# PMIC.net
KiCad netlist of a schematic drawn in Altium Designer
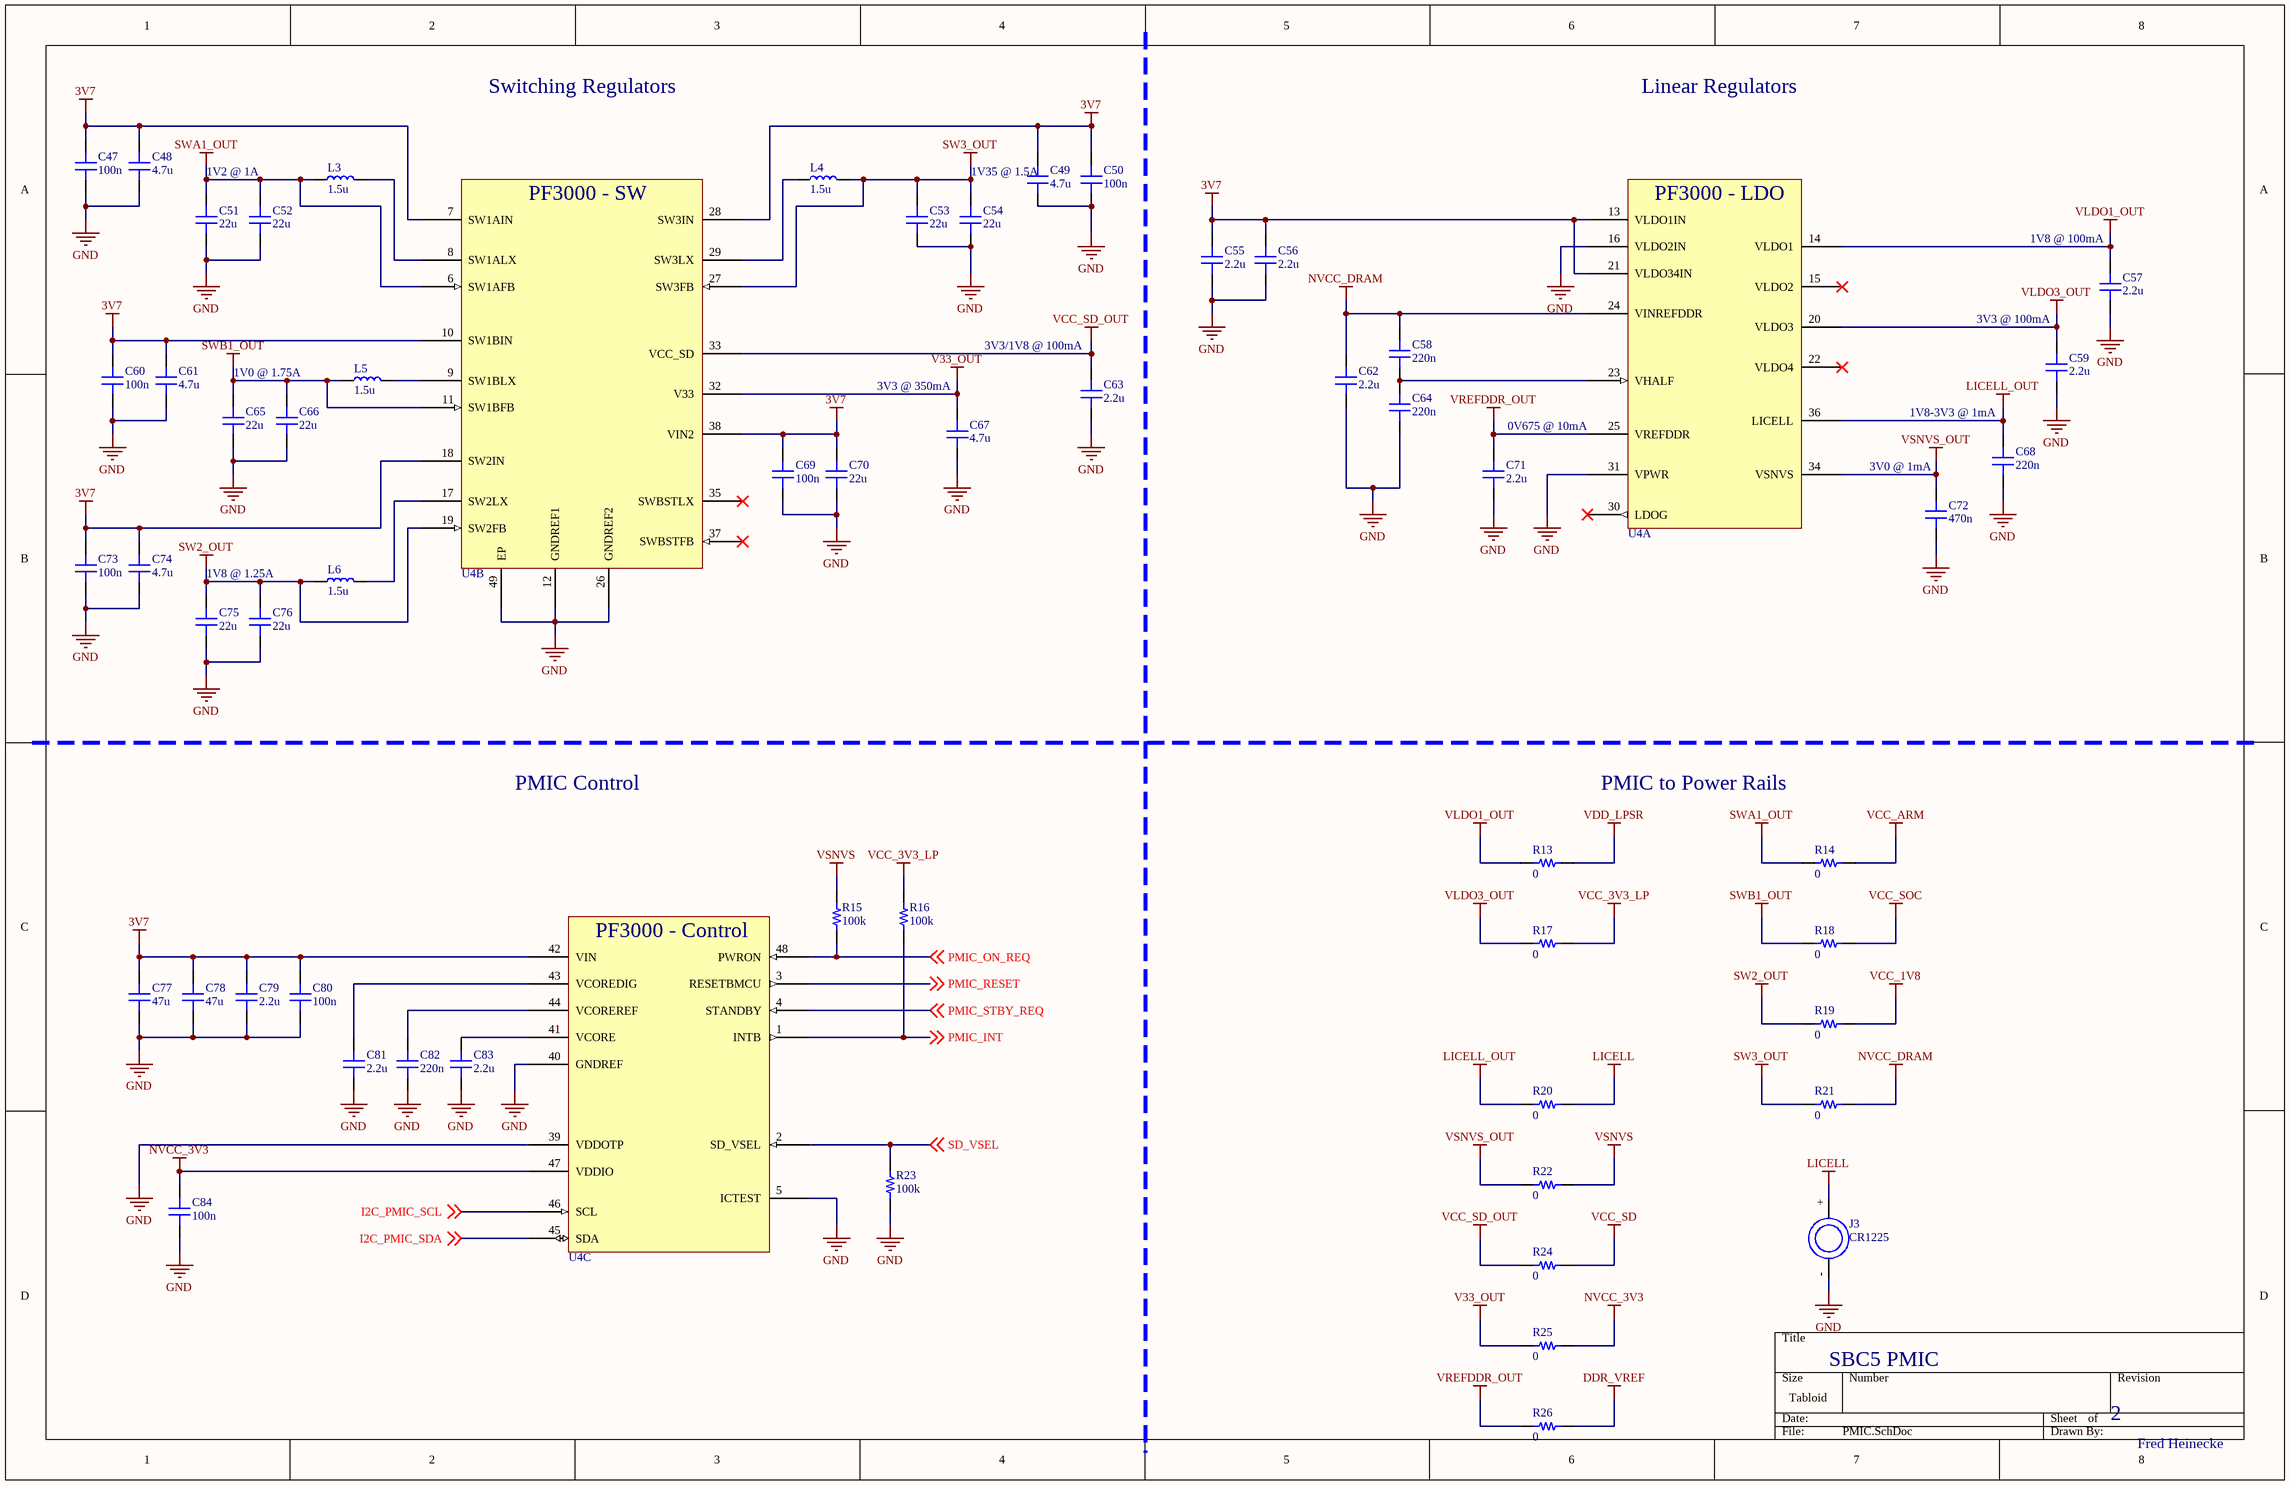
[diagram p0: PMIC.SchDoc]

(export (version "E")
  (design (tool "Eeschema 10.0.6"))
  (components
    (comp (ref "C47")
      (value "100n")
      (footprint "C0201")
      (description "Multilayer Ceramic Capacitors MLCC - SMD/SMT 0201 0.10uF 16volts *Derate Voltage/Temp")
      (fields
        (field (name "MANUFACTURER") "Murata")
        (field (name "MANUFACTURER PART NUMBER") "GRM033R61C104KE84D")
      )
      (libsource (lib "SBC5") (part "GRM033R61C104KE84D"))
    )
    (comp (ref "C48")
      (value "4.7u")
      (footprint "C0603")
      (description "Cap Ceramic 4.7uF 10V X5R 10% Pad SMD 0603 85C T/R")
      (fields
        (field (name "MANUFACTURER") "Samsung")
        (field (name "MANUFACTURER PART NUMBER") "CL10A475KP8NNNC")
      )
      (libsource (lib "SBC5") (part "CL10A475KP8NNNC"))
    )
    (comp (ref "C49")
      (value "4.7u")
      (footprint "C0603")
      (description "Cap Ceramic 4.7uF 10V X5R 10% Pad SMD 0603 85C T/R")
      (fields
        (field (name "MANUFACTURER") "Samsung")
        (field (name "MANUFACTURER PART NUMBER") "CL10A475KP8NNNC")
      )
      (libsource (lib "SBC5") (part "CL10A475KP8NNNC"))
    )
    (comp (ref "C50")
      (value "100n")
      (footprint "C0201")
      (description "Multilayer Ceramic Capacitors MLCC - SMD/SMT 0201 0.10uF 16volts *Derate Voltage/Temp")
      (fields
        (field (name "MANUFACTURER") "Murata")
        (field (name "MANUFACTURER PART NUMBER") "GRM033R61C104KE84D")
      )
      (libsource (lib "SBC5") (part "GRM033R61C104KE84D"))
    )
    (comp (ref "C51")
      (value "22u")
      (footprint "C0603")
      (description "0603 22 uF 10 V ±20% Tolerance X5R Multilayer Ceramic Chip Capacitor")
      (fields
        (field (name "MANUFACTURER") "Murata")
        (field (name "MANUFACTURER PART NUMBER") "GRM188R61A226ME15D")
      )
      (libsource (lib "SBC5") (part "GRM188R61A226ME15D"))
    )
    (comp (ref "C52")
      (value "22u")
      (footprint "C0603")
      (description "0603 22 uF 10 V ±20% Tolerance X5R Multilayer Ceramic Chip Capacitor")
      (fields
        (field (name "MANUFACTURER") "Murata")
        (field (name "MANUFACTURER PART NUMBER") "GRM188R61A226ME15D")
      )
      (libsource (lib "SBC5") (part "GRM188R61A226ME15D"))
    )
    (comp (ref "C53")
      (value "22u")
      (footprint "C0603")
      (description "0603 22 uF 10 V ±20% Tolerance X5R Multilayer Ceramic Chip Capacitor")
      (fields
        (field (name "MANUFACTURER") "Murata")
        (field (name "MANUFACTURER PART NUMBER") "GRM188R61A226ME15D")
      )
      (libsource (lib "SBC5") (part "GRM188R61A226ME15D"))
    )
    (comp (ref "C54")
      (value "22u")
      (footprint "C0603")
      (description "0603 22 uF 10 V ±20% Tolerance X5R Multilayer Ceramic Chip Capacitor")
      (fields
        (field (name "MANUFACTURER") "Murata")
        (field (name "MANUFACTURER PART NUMBER") "GRM188R61A226ME15D")
      )
      (libsource (lib "SBC5") (part "GRM188R61A226ME15D"))
    )
    (comp (ref "C55")
      (value "2.2u")
      (footprint "C0402")
      (description "TAIYO YUDEN         LMK105BJ225MV-F            CERAMIC CAPACITOR, 2.2UF, 10V, X5R, 20%, 0402")
      (fields
        (field (name "MANUFACTURER") "Taiyo Yuden")
        (field (name "MANUFACTURER PART NUMBER") "LMK105BJ225MV-F")
      )
      (libsource (lib "SBC5") (part "LMK105BJ225MV-F"))
    )
    (comp (ref "C56")
      (value "2.2u")
      (footprint "C0402")
      (description "TAIYO YUDEN         LMK105BJ225MV-F            CERAMIC CAPACITOR, 2.2UF, 10V, X5R, 20%, 0402")
      (fields
        (field (name "MANUFACTURER") "Taiyo Yuden")
        (field (name "MANUFACTURER PART NUMBER") "LMK105BJ225MV-F")
      )
      (libsource (lib "SBC5") (part "LMK105BJ225MV-F"))
    )
    (comp (ref "C57")
      (value "2.2u")
      (footprint "C0402")
      (description "TAIYO YUDEN         LMK105BJ225MV-F            CERAMIC CAPACITOR, 2.2UF, 10V, X5R, 20%, 0402")
      (fields
        (field (name "MANUFACTURER") "Taiyo Yuden")
        (field (name "MANUFACTURER PART NUMBER") "LMK105BJ225MV-F")
      )
      (libsource (lib "SBC5") (part "LMK105BJ225MV-F"))
    )
    (comp (ref "C58")
      (value "220n")
      (footprint "C0201")
      (description "Cap Ceramic Monolithic 0.22uF 16VDC 10% SMD Paper T/R")
      (fields
        (field (name "MANUFACTURER") "Murata")
        (field (name "MANUFACTURER PART NUMBER") "GRM033R61C224KE14D")
      )
      (libsource (lib "SBC5") (part "GRM033R61C224KE14D"))
    )
    (comp (ref "C59")
      (value "2.2u")
      (footprint "C0402")
      (description "TAIYO YUDEN         LMK105BJ225MV-F            CERAMIC CAPACITOR, 2.2UF, 10V, X5R, 20%, 0402")
      (fields
        (field (name "MANUFACTURER") "Taiyo Yuden")
        (field (name "MANUFACTURER PART NUMBER") "LMK105BJ225MV-F")
      )
      (libsource (lib "SBC5") (part "LMK105BJ225MV-F"))
    )
    (comp (ref "C60")
      (value "100n")
      (footprint "C0201")
      (description "Multilayer Ceramic Capacitors MLCC - SMD/SMT 0201 0.10uF 16volts *Derate Voltage/Temp")
      (fields
        (field (name "MANUFACTURER") "Murata")
        (field (name "MANUFACTURER PART NUMBER") "GRM033R61C104KE84D")
      )
      (libsource (lib "SBC5") (part "GRM033R61C104KE84D"))
    )
    (comp (ref "C61")
      (value "4.7u")
      (footprint "C0603")
      (description "Cap Ceramic 4.7uF 10V X5R 10% Pad SMD 0603 85C T/R")
      (fields
        (field (name "MANUFACTURER") "Samsung")
        (field (name "MANUFACTURER PART NUMBER") "CL10A475KP8NNNC")
      )
      (libsource (lib "SBC5") (part "CL10A475KP8NNNC"))
    )
    (comp (ref "C62")
      (value "2.2u")
      (footprint "C0402")
      (description "TAIYO YUDEN         LMK105BJ225MV-F            CERAMIC CAPACITOR, 2.2UF, 10V, X5R, 20%, 0402")
      (fields
        (field (name "MANUFACTURER") "Taiyo Yuden")
        (field (name "MANUFACTURER PART NUMBER") "LMK105BJ225MV-F")
      )
      (libsource (lib "SBC5") (part "LMK105BJ225MV-F"))
    )
    (comp (ref "C63")
      (value "2.2u")
      (footprint "C0402")
      (description "TAIYO YUDEN         LMK105BJ225MV-F            CERAMIC CAPACITOR, 2.2UF, 10V, X5R, 20%, 0402")
      (fields
        (field (name "MANUFACTURER") "Taiyo Yuden")
        (field (name "MANUFACTURER PART NUMBER") "LMK105BJ225MV-F")
      )
      (libsource (lib "SBC5") (part "LMK105BJ225MV-F"))
    )
    (comp (ref "C64")
      (value "220n")
      (footprint "C0201")
      (description "Cap Ceramic Monolithic 0.22uF 16VDC 10% SMD Paper T/R")
      (fields
        (field (name "MANUFACTURER") "Murata")
        (field (name "MANUFACTURER PART NUMBER") "GRM033R61C224KE14D")
      )
      (libsource (lib "SBC5") (part "GRM033R61C224KE14D"))
    )
    (comp (ref "C65")
      (value "22u")
      (footprint "C0603")
      (description "0603 22 uF 10 V ±20% Tolerance X5R Multilayer Ceramic Chip Capacitor")
      (fields
        (field (name "MANUFACTURER") "Murata")
        (field (name "MANUFACTURER PART NUMBER") "GRM188R61A226ME15D")
      )
      (libsource (lib "SBC5") (part "GRM188R61A226ME15D"))
    )
    (comp (ref "C66")
      (value "22u")
      (footprint "C0603")
      (description "0603 22 uF 10 V ±20% Tolerance X5R Multilayer Ceramic Chip Capacitor")
      (fields
        (field (name "MANUFACTURER") "Murata")
        (field (name "MANUFACTURER PART NUMBER") "GRM188R61A226ME15D")
      )
      (libsource (lib "SBC5") (part "GRM188R61A226ME15D"))
    )
    (comp (ref "C67")
      (value "4.7u")
      (footprint "C0603")
      (description "Cap Ceramic 4.7uF 10V X5R 10% Pad SMD 0603 85C T/R")
      (fields
        (field (name "MANUFACTURER") "Samsung")
        (field (name "MANUFACTURER PART NUMBER") "CL10A475KP8NNNC")
      )
      (libsource (lib "SBC5") (part "CL10A475KP8NNNC"))
    )
    (comp (ref "C68")
      (value "220n")
      (footprint "C0201")
      (description "Cap Ceramic Monolithic 0.22uF 16VDC 10% SMD Paper T/R")
      (fields
        (field (name "MANUFACTURER") "Murata")
        (field (name "MANUFACTURER PART NUMBER") "GRM033R61C224KE14D")
      )
      (libsource (lib "SBC5") (part "GRM033R61C224KE14D"))
    )
    (comp (ref "C69")
      (value "100n")
      (footprint "C0201")
      (description "Multilayer Ceramic Capacitors MLCC - SMD/SMT 0201 0.10uF 16volts *Derate Voltage/Temp")
      (fields
        (field (name "MANUFACTURER") "Murata")
        (field (name "MANUFACTURER PART NUMBER") "GRM033R61C104KE84D")
      )
      (libsource (lib "SBC5") (part "GRM033R61C104KE84D"))
    )
    (comp (ref "C70")
      (value "22u")
      (footprint "C0603")
      (description "0603 22 uF 10 V ±20% Tolerance X5R Multilayer Ceramic Chip Capacitor")
      (fields
        (field (name "MANUFACTURER") "Murata")
        (field (name "MANUFACTURER PART NUMBER") "GRM188R61A226ME15D")
      )
      (libsource (lib "SBC5") (part "GRM188R61A226ME15D"))
    )
    (comp (ref "C71")
      (value "2.2u")
      (footprint "C0402")
      (description "TAIYO YUDEN         LMK105BJ225MV-F            CERAMIC CAPACITOR, 2.2UF, 10V, X5R, 20%, 0402")
      (fields
        (field (name "MANUFACTURER") "Taiyo Yuden")
        (field (name "MANUFACTURER PART NUMBER") "LMK105BJ225MV-F")
      )
      (libsource (lib "SBC5") (part "LMK105BJ225MV-F"))
    )
    (comp (ref "C72")
      (value "470n")
      (footprint "C0402")
      (description "Cap Ceramic 0.47uF 10V X5R 10% SMD 0402 85C T/R")
      (fields
        (field (name "MANUFACTURER") "Samsung")
        (field (name "MANUFACTURER PART NUMBER") "CL05A474KP5NNNC")
      )
      (libsource (lib "SBC5") (part "CL05A474KP5NNNC"))
    )
    (comp (ref "C73")
      (value "100n")
      (footprint "C0201")
      (description "Multilayer Ceramic Capacitors MLCC - SMD/SMT 0201 0.10uF 16volts *Derate Voltage/Temp")
      (fields
        (field (name "MANUFACTURER") "Murata")
        (field (name "MANUFACTURER PART NUMBER") "GRM033R61C104KE84D")
      )
      (libsource (lib "SBC5") (part "GRM033R61C104KE84D"))
    )
    (comp (ref "C74")
      (value "4.7u")
      (footprint "C0603")
      (description "Cap Ceramic 4.7uF 10V X5R 10% Pad SMD 0603 85C T/R")
      (fields
        (field (name "MANUFACTURER") "Samsung")
        (field (name "MANUFACTURER PART NUMBER") "CL10A475KP8NNNC")
      )
      (libsource (lib "SBC5") (part "CL10A475KP8NNNC"))
    )
    (comp (ref "C75")
      (value "22u")
      (footprint "C0603")
      (description "0603 22 uF 10 V ±20% Tolerance X5R Multilayer Ceramic Chip Capacitor")
      (fields
        (field (name "MANUFACTURER") "Murata")
        (field (name "MANUFACTURER PART NUMBER") "GRM188R61A226ME15D")
      )
      (libsource (lib "SBC5") (part "GRM188R61A226ME15D"))
    )
    (comp (ref "C76")
      (value "22u")
      (footprint "C0603")
      (description "0603 22 uF 10 V ±20% Tolerance X5R Multilayer Ceramic Chip Capacitor")
      (fields
        (field (name "MANUFACTURER") "Murata")
        (field (name "MANUFACTURER PART NUMBER") "GRM188R61A226ME15D")
      )
      (libsource (lib "SBC5") (part "GRM188R61A226ME15D"))
    )
    (comp (ref "C77")
      (value "47u")
      (footprint "C0805")
      (fields
        (field (name "MANUFACTURER") "TDK")
        (field (name "MANUFACTURER PART NUMBER") "C2012X5R1A476M125AC")
        (field (name "TOLERANCE") "20%")
      )
      (libsource (lib "SBC5") (part "C2012X5R1A476M125AC"))
    )
    (comp (ref "C78")
      (value "47u")
      (footprint "C0805")
      (fields
        (field (name "MANUFACTURER") "TDK")
        (field (name "MANUFACTURER PART NUMBER") "C2012X5R1A476M125AC")
        (field (name "TOLERANCE") "20%")
      )
      (libsource (lib "SBC5") (part "C2012X5R1A476M125AC"))
    )
    (comp (ref "C79")
      (value "2.2u")
      (footprint "C0402")
      (description "TAIYO YUDEN         LMK105BJ225MV-F            CERAMIC CAPACITOR, 2.2UF, 10V, X5R, 20%, 0402")
      (fields
        (field (name "MANUFACTURER") "Taiyo Yuden")
        (field (name "MANUFACTURER PART NUMBER") "LMK105BJ225MV-F")
      )
      (libsource (lib "SBC5") (part "LMK105BJ225MV-F"))
    )
    (comp (ref "C80")
      (value "100n")
      (footprint "C0201")
      (description "Multilayer Ceramic Capacitors MLCC - SMD/SMT 0201 0.10uF 16volts *Derate Voltage/Temp")
      (fields
        (field (name "MANUFACTURER") "Murata")
        (field (name "MANUFACTURER PART NUMBER") "GRM033R61C104KE84D")
      )
      (libsource (lib "SBC5") (part "GRM033R61C104KE84D"))
    )
    (comp (ref "C81")
      (value "2.2u")
      (footprint "C0402")
      (description "TAIYO YUDEN         LMK105BJ225MV-F            CERAMIC CAPACITOR, 2.2UF, 10V, X5R, 20%, 0402")
      (fields
        (field (name "MANUFACTURER") "Taiyo Yuden")
        (field (name "MANUFACTURER PART NUMBER") "LMK105BJ225MV-F")
      )
      (libsource (lib "SBC5") (part "LMK105BJ225MV-F"))
    )
    (comp (ref "C82")
      (value "220n")
      (footprint "C0201")
      (description "Cap Ceramic Monolithic 0.22uF 16VDC 10% SMD Paper T/R")
      (fields
        (field (name "MANUFACTURER") "Murata")
        (field (name "MANUFACTURER PART NUMBER") "GRM033R61C224KE14D")
      )
      (libsource (lib "SBC5") (part "GRM033R61C224KE14D"))
    )
    (comp (ref "C83")
      (value "2.2u")
      (footprint "C0402")
      (description "TAIYO YUDEN         LMK105BJ225MV-F            CERAMIC CAPACITOR, 2.2UF, 10V, X5R, 20%, 0402")
      (fields
        (field (name "MANUFACTURER") "Taiyo Yuden")
        (field (name "MANUFACTURER PART NUMBER") "LMK105BJ225MV-F")
      )
      (libsource (lib "SBC5") (part "LMK105BJ225MV-F"))
    )
    (comp (ref "C84")
      (value "100n")
      (footprint "C0201")
      (description "Multilayer Ceramic Capacitors MLCC - SMD/SMT 0201 0.10uF 16volts *Derate Voltage/Temp")
      (fields
        (field (name "MANUFACTURER") "Murata")
        (field (name "MANUFACTURER PART NUMBER") "GRM033R61C104KE84D")
      )
      (libsource (lib "SBC5") (part "GRM033R61C104KE84D"))
    )
    (comp (ref "J3")
      (value "CR1225")
      (footprint "BAT-HLD-012-THM")
      (description "BATTERY RETAINER COIN PC PIN")
      (fields
        (field (name "MANUFACTURER") "Linx")
        (field (name "MANUFACTURER PART NUMBER") "BAT-HLD-012-THM")
      )
      (libsource (lib "SBC5") (part "BAT-HLD-012-THM"))
    )
    (comp (ref "L3")
      (value "1.5u")
      (footprint "L0806")
      (description "Inductor Power Shielded Wirewound 1.5uH 20% 1MHz Metal 2.1A 0.091Ohm DCR 0806 T/R")
      (fields
        (field (name "MANUFACTURER") "Murata")
        (field (name "MANUFACTURER PART NUMBER") "DFE201610E-1R5M=P2")
      )
      (libsource (lib "SBC5") (part "DFE201610E-1R5M=P2"))
    )
    (comp (ref "L4")
      (value "1.5u")
      (footprint "L0806")
      (description "Inductor Power Shielded Wirewound 1.5uH 20% 1MHz Metal 2.1A 0.091Ohm DCR 0806 T/R")
      (fields
        (field (name "MANUFACTURER") "Murata")
        (field (name "MANUFACTURER PART NUMBER") "DFE201610E-1R5M=P2")
      )
      (libsource (lib "") (part "DFE201610E-1R5M=P2_1"))
    )
    (comp (ref "L5")
      (value "1.5u")
      (footprint "L0806")
      (description "Inductor Power Shielded Wirewound 1.5uH 20% 1MHz Metal 2.1A 0.091Ohm DCR 0806 T/R")
      (fields
        (field (name "MANUFACTURER") "Murata")
        (field (name "MANUFACTURER PART NUMBER") "DFE201610E-1R5M=P2")
      )
      (libsource (lib "SBC5") (part "DFE201610E-1R5M=P2"))
    )
    (comp (ref "L6")
      (value "1.5u")
      (footprint "L0806")
      (description "Inductor Power Shielded Wirewound 1.5uH 20% 1MHz Metal 2.1A 0.091Ohm DCR 0806 T/R")
      (fields
        (field (name "MANUFACTURER") "Murata")
        (field (name "MANUFACTURER PART NUMBER") "DFE201610E-1R5M=P2")
      )
      (libsource (lib "SBC5") (part "DFE201610E-1R5M=P2"))
    )
    (comp (ref "R13")
      (value "0")
      (footprint "R0402")
      (description "RES 0 OHM JUMPER 1/16W 0402")
      (fields
        (field (name "MANUFACTURER") "Stackpole Electronics")
        (field (name "MANUFACTURER PART NUMBER") "RMCF0402ZT0R00")
      )
      (libsource (lib "SBC5") (part "RMCF0402ZT0R00"))
    )
    (comp (ref "R14")
      (value "0")
      (footprint "R0402")
      (description "RES 0 OHM JUMPER 1/16W 0402")
      (fields
        (field (name "MANUFACTURER") "Stackpole Electronics")
        (field (name "MANUFACTURER PART NUMBER") "RMCF0402ZT0R00")
      )
      (libsource (lib "SBC5") (part "RMCF0402ZT0R00"))
    )
    (comp (ref "R15")
      (value "100k")
      (footprint "R0201")
      (description "PANASONIC - ERJ1GNF1003C - RES, 100K, 1%, 0.05W, 0201, THICK FILM")
      (fields
        (field (name "MANUFACTURER") "Panasonic")
        (field (name "MANUFACTURER PART NUMBER") "ERJ-1GNF1003C")
      )
      (libsource (lib "SBC5") (part "ERJ-1GNF1003C"))
    )
    (comp (ref "R16")
      (value "100k")
      (footprint "R0201")
      (description "PANASONIC - ERJ1GNF1003C - RES, 100K, 1%, 0.05W, 0201, THICK FILM")
      (fields
        (field (name "MANUFACTURER") "Panasonic")
        (field (name "MANUFACTURER PART NUMBER") "ERJ-1GNF1003C")
      )
      (libsource (lib "SBC5") (part "ERJ-1GNF1003C"))
    )
    (comp (ref "R17")
      (value "0")
      (footprint "R0402")
      (description "RES 0 OHM JUMPER 1/16W 0402")
      (fields
        (field (name "MANUFACTURER") "Stackpole Electronics")
        (field (name "MANUFACTURER PART NUMBER") "RMCF0402ZT0R00")
      )
      (libsource (lib "SBC5") (part "RMCF0402ZT0R00"))
    )
    (comp (ref "R18")
      (value "0")
      (footprint "R0402")
      (description "RES 0 OHM JUMPER 1/16W 0402")
      (fields
        (field (name "MANUFACTURER") "Stackpole Electronics")
        (field (name "MANUFACTURER PART NUMBER") "RMCF0402ZT0R00")
      )
      (libsource (lib "SBC5") (part "RMCF0402ZT0R00"))
    )
    (comp (ref "R19")
      (value "0")
      (footprint "R0402")
      (description "RES 0 OHM JUMPER 1/16W 0402")
      (fields
        (field (name "MANUFACTURER") "Stackpole Electronics")
        (field (name "MANUFACTURER PART NUMBER") "RMCF0402ZT0R00")
      )
      (libsource (lib "SBC5") (part "RMCF0402ZT0R00"))
    )
    (comp (ref "R20")
      (value "0")
      (footprint "R0402")
      (description "RES 0 OHM JUMPER 1/16W 0402")
      (fields
        (field (name "MANUFACTURER") "Stackpole Electronics")
        (field (name "MANUFACTURER PART NUMBER") "RMCF0402ZT0R00")
      )
      (libsource (lib "SBC5") (part "RMCF0402ZT0R00"))
    )
    (comp (ref "R21")
      (value "0")
      (footprint "R0402")
      (description "RES 0 OHM JUMPER 1/16W 0402")
      (fields
        (field (name "MANUFACTURER") "Stackpole Electronics")
        (field (name "MANUFACTURER PART NUMBER") "RMCF0402ZT0R00")
      )
      (libsource (lib "SBC5") (part "RMCF0402ZT0R00"))
    )
    (comp (ref "R22")
      (value "0")
      (footprint "R0402")
      (description "RES 0 OHM JUMPER 1/16W 0402")
      (fields
        (field (name "MANUFACTURER") "Stackpole Electronics")
        (field (name "MANUFACTURER PART NUMBER") "RMCF0402ZT0R00")
      )
      (libsource (lib "SBC5") (part "RMCF0402ZT0R00"))
    )
    (comp (ref "R23")
      (value "100k")
      (footprint "R0201")
      (description "PANASONIC - ERJ1GNF1003C - RES, 100K, 1%, 0.05W, 0201, THICK FILM")
      (fields
        (field (name "MANUFACTURER") "Panasonic")
        (field (name "MANUFACTURER PART NUMBER") "ERJ-1GNF1003C")
      )
      (libsource (lib "SBC5") (part "ERJ-1GNF1003C"))
    )
    (comp (ref "R24")
      (value "0")
      (footprint "R0402")
      (description "RES 0 OHM JUMPER 1/16W 0402")
      (fields
        (field (name "MANUFACTURER") "Stackpole Electronics")
        (field (name "MANUFACTURER PART NUMBER") "RMCF0402ZT0R00")
      )
      (libsource (lib "SBC5") (part "RMCF0402ZT0R00"))
    )
    (comp (ref "R25")
      (value "0")
      (footprint "R0402")
      (description "RES 0 OHM JUMPER 1/16W 0402")
      (fields
        (field (name "MANUFACTURER") "Stackpole Electronics")
        (field (name "MANUFACTURER PART NUMBER") "RMCF0402ZT0R00")
      )
      (libsource (lib "SBC5") (part "RMCF0402ZT0R00"))
    )
    (comp (ref "R26")
      (value "0")
      (footprint "R0402")
      (description "RES 0 OHM JUMPER 1/16W 0402")
      (fields
        (field (name "MANUFACTURER") "Stackpole Electronics")
        (field (name "MANUFACTURER PART NUMBER") "RMCF0402ZT0R00")
      )
      (libsource (lib "SBC5") (part "RMCF0402ZT0R00"))
    )
    (comp (ref "U4")
      (value "PMIC")
      (footprint "PQFN50P700X700X90_HS-49N")
      (description "Power Management IC, i.MX7, pre-prog, 4 buck, 6 LDO, 1 boost, QFN 48, Tray")
      (fields
        (field (name "MANUFACTURER") "NXP Freescale")
        (field (name "MANUFACTURER PART NUMBER") "MC34PF3000A1EP")
      )
      (libsource (lib "SBC5") (part "MC34PF3000A4EP"))
    )
  )
  (nets
    (net (code "1") (name "3V7") (class "Default")
      (node (ref "C47") (pin "2") (pinfunction "2_2") (pintype "passive"))
      (node (ref "C48") (pin "2") (pinfunction "2_2") (pintype "passive"))
      (node (ref "C49") (pin "2") (pinfunction "2_2") (pintype "passive"))
      (node (ref "C50") (pin "2") (pinfunction "2_2") (pintype "passive"))
      (node (ref "C55") (pin "2") (pinfunction "2_2") (pintype "passive"))
      (node (ref "C56") (pin "2") (pinfunction "2_2") (pintype "passive"))
      (node (ref "C60") (pin "2") (pinfunction "2_2") (pintype "passive"))
      (node (ref "C61") (pin "2") (pinfunction "2_2") (pintype "passive"))
      (node (ref "C69") (pin "2") (pinfunction "2_2") (pintype "passive"))
      (node (ref "C70") (pin "2") (pinfunction "2_2") (pintype "passive"))
      (node (ref "C73") (pin "2") (pinfunction "2_2") (pintype "passive"))
      (node (ref "C74") (pin "2") (pinfunction "2_2") (pintype "passive"))
      (node (ref "C77") (pin "2") (pinfunction "2_2") (pintype "passive"))
      (node (ref "C78") (pin "2") (pinfunction "2_2") (pintype "passive"))
      (node (ref "C79") (pin "2") (pinfunction "2_2") (pintype "passive"))
      (node (ref "C80") (pin "2") (pinfunction "2_2") (pintype "passive"))
      (node (ref "U4") (pin "10") (pinfunction "SW1BIN_10") (pintype "power_in"))
      (node (ref "U4") (pin "13") (pinfunction "VLDO1IN_13") (pintype "power_in"))
      (node (ref "U4") (pin "18") (pinfunction "SW2IN_18") (pintype "power_in"))
      (node (ref "U4") (pin "21") (pinfunction "VLDO34IN_21") (pintype "power_in"))
      (node (ref "U4") (pin "28") (pinfunction "SW3IN_28") (pintype "power_in"))
      (node (ref "U4") (pin "38") (pinfunction "VIN2_38") (pintype "power_in"))
      (node (ref "U4") (pin "42") (pinfunction "VIN_42") (pintype "passive"))
      (node (ref "U4") (pin "7") (pinfunction "SW1AIN_7") (pintype "power_in"))
    )
    (net (code "2") (name "DDR_VREF") (class "Default")
      (node (ref "R26") (pin "2") (pinfunction "2_2") (pintype "passive"))
    )
    (net (code "3") (name "GND") (class "Default")
      (node (ref "C47") (pin "1") (pinfunction "1_1") (pintype "passive"))
      (node (ref "C48") (pin "1") (pinfunction "1_1") (pintype "passive"))
      (node (ref "C49") (pin "1") (pinfunction "1_1") (pintype "passive"))
      (node (ref "C50") (pin "1") (pinfunction "1_1") (pintype "passive"))
      (node (ref "C51") (pin "1") (pinfunction "1_1") (pintype "passive"))
      (node (ref "C52") (pin "1") (pinfunction "1_1") (pintype "passive"))
      (node (ref "C53") (pin "1") (pinfunction "1_1") (pintype "passive"))
      (node (ref "C54") (pin "1") (pinfunction "1_1") (pintype "passive"))
      (node (ref "C55") (pin "1") (pinfunction "1_1") (pintype "passive"))
      (node (ref "C56") (pin "1") (pinfunction "1_1") (pintype "passive"))
      (node (ref "C57") (pin "1") (pinfunction "1_1") (pintype "passive"))
      (node (ref "C59") (pin "1") (pinfunction "1_1") (pintype "passive"))
      (node (ref "C60") (pin "1") (pinfunction "1_1") (pintype "passive"))
      (node (ref "C61") (pin "1") (pinfunction "1_1") (pintype "passive"))
      (node (ref "C62") (pin "1") (pinfunction "1_1") (pintype "passive"))
      (node (ref "C63") (pin "1") (pinfunction "1_1") (pintype "passive"))
      (node (ref "C64") (pin "1") (pinfunction "1_1") (pintype "passive"))
      (node (ref "C65") (pin "1") (pinfunction "1_1") (pintype "passive"))
      (node (ref "C66") (pin "1") (pinfunction "1_1") (pintype "passive"))
      (node (ref "C67") (pin "1") (pinfunction "1_1") (pintype "passive"))
      (node (ref "C68") (pin "1") (pinfunction "1_1") (pintype "passive"))
      (node (ref "C69") (pin "1") (pinfunction "1_1") (pintype "passive"))
      (node (ref "C70") (pin "1") (pinfunction "1_1") (pintype "passive"))
      (node (ref "C71") (pin "1") (pinfunction "1_1") (pintype "passive"))
      (node (ref "C72") (pin "1") (pinfunction "1_1") (pintype "passive"))
      (node (ref "C73") (pin "1") (pinfunction "1_1") (pintype "passive"))
      (node (ref "C74") (pin "1") (pinfunction "1_1") (pintype "passive"))
      (node (ref "C75") (pin "1") (pinfunction "1_1") (pintype "passive"))
      (node (ref "C76") (pin "1") (pinfunction "1_1") (pintype "passive"))
      (node (ref "C77") (pin "1") (pinfunction "1_1") (pintype "passive"))
      (node (ref "C78") (pin "1") (pinfunction "1_1") (pintype "passive"))
      (node (ref "C79") (pin "1") (pinfunction "1_1") (pintype "passive"))
      (node (ref "C80") (pin "1") (pinfunction "1_1") (pintype "passive"))
      (node (ref "C81") (pin "1") (pinfunction "1_1") (pintype "passive"))
      (node (ref "C82") (pin "1") (pinfunction "1_1") (pintype "passive"))
      (node (ref "C83") (pin "1") (pinfunction "1_1") (pintype "passive"))
      (node (ref "C84") (pin "1") (pinfunction "1_1") (pintype "passive"))
      (node (ref "J3") (pin "-") (pinfunction "-_-") (pintype "passive"))
      (node (ref "R23") (pin "1") (pinfunction "1_1") (pintype "passive"))
      (node (ref "U4") (pin "12") (pinfunction "GNDREF1_12") (pintype "passive"))
      (node (ref "U4") (pin "16") (pinfunction "VLDO2IN_16") (pintype "power_in"))
      (node (ref "U4") (pin "26") (pinfunction "GNDREF2_26") (pintype "passive"))
      (node (ref "U4") (pin "31") (pinfunction "VPWR_31") (pintype "power_in"))
      (node (ref "U4") (pin "39") (pinfunction "VDDOTP_39") (pintype "passive"))
      (node (ref "U4") (pin "40") (pinfunction "GNDREF_40") (pintype "passive"))
      (node (ref "U4") (pin "49") (pinfunction "EP_49") (pintype "passive"))
      (node (ref "U4") (pin "5") (pinfunction "ICTEST_5") (pintype "passive"))
    )
    (net (code "4") (name "I2C_PMIC_SCL") (class "Default")
      (node (ref "U4") (pin "46") (pinfunction "SCL_46") (pintype "input"))
    )
    (net (code "5") (name "I2C_PMIC_SDA") (class "Default")
      (node (ref "U4") (pin "45") (pinfunction "SDA_45") (pintype "bidirectional"))
    )
    (net (code "6") (name "LICELL") (class "Default")
      (node (ref "J3") (pin "+") (pinfunction "+_+") (pintype "power_in"))
      (node (ref "R20") (pin "2") (pinfunction "2_2") (pintype "passive"))
    )
    (net (code "7") (name "LICELL_OUT") (class "Default")
      (node (ref "C68") (pin "2") (pinfunction "2_2") (pintype "passive"))
      (node (ref "R20") (pin "1") (pinfunction "1_1") (pintype "passive"))
      (node (ref "U4") (pin "36") (pinfunction "LICELL_36") (pintype "power_in"))
    )
    (net (code "8") (name "NVCC_3V3") (class "Default")
      (node (ref "C84") (pin "2") (pinfunction "2_2") (pintype "passive"))
      (node (ref "R25") (pin "2") (pinfunction "2_2") (pintype "passive"))
      (node (ref "U4") (pin "47") (pinfunction "VDDIO_47") (pintype "power_in"))
    )
    (net (code "9") (name "NVCC_DRAM") (class "Default")
      (node (ref "C58") (pin "2") (pinfunction "2_2") (pintype "passive"))
      (node (ref "C62") (pin "2") (pinfunction "2_2") (pintype "passive"))
      (node (ref "R21") (pin "2") (pinfunction "2_2") (pintype "passive"))
      (node (ref "U4") (pin "24") (pinfunction "VINREFDDR_24") (pintype "passive"))
    )
    (net (code "10") (name "Net-(U4A-VHALF)") (class "Default")
      (node (ref "C58") (pin "1") (pinfunction "1_1") (pintype "passive"))
      (node (ref "C64") (pin "2") (pinfunction "2_2") (pintype "passive"))
      (node (ref "U4") (pin "23") (pinfunction "VHALF_23") (pintype "input"))
    )
    (net (code "11") (name "Net-(U4B-SW1ALX)") (class "Default")
      (node (ref "L3") (pin "2") (pinfunction "2_2") (pintype "passive"))
      (node (ref "U4") (pin "8") (pinfunction "SW1ALX_8") (pintype "power_in"))
    )
    (net (code "12") (name "Net-(U4B-SW1BLX)") (class "Default")
      (node (ref "L5") (pin "2") (pinfunction "2_2") (pintype "passive"))
      (node (ref "U4") (pin "9") (pinfunction "SW1BLX_9") (pintype "power_in"))
    )
    (net (code "13") (name "Net-(U4B-SW2LX)") (class "Default")
      (node (ref "L6") (pin "2") (pinfunction "2_2") (pintype "passive"))
      (node (ref "U4") (pin "17") (pinfunction "SW2LX_17") (pintype "power_in"))
    )
    (net (code "14") (name "Net-(U4B-SW3LX)") (class "Default")
      (node (ref "L4") (pin "2") (pinfunction "2_2") (pintype "passive"))
      (node (ref "U4") (pin "29") (pinfunction "SW3LX_29") (pintype "power_in"))
    )
    (net (code "15") (name "Net-(U4C-VCORE)") (class "Default")
      (node (ref "C83") (pin "2") (pinfunction "2_2") (pintype "passive"))
      (node (ref "U4") (pin "41") (pinfunction "VCORE_41") (pintype "passive"))
    )
    (net (code "16") (name "Net-(U4C-VCOREDIG)") (class "Default")
      (node (ref "C81") (pin "2") (pinfunction "2_2") (pintype "passive"))
      (node (ref "U4") (pin "43") (pinfunction "VCOREDIG_43") (pintype "passive"))
    )
    (net (code "17") (name "Net-(U4C-VCOREREF)") (class "Default")
      (node (ref "C82") (pin "2") (pinfunction "2_2") (pintype "passive"))
      (node (ref "U4") (pin "44") (pinfunction "VCOREREF_44") (pintype "passive"))
    )
    (net (code "18") (name "PMIC_INT") (class "Default")
      (node (ref "R16") (pin "1") (pinfunction "1_1") (pintype "passive"))
      (node (ref "U4") (pin "1") (pinfunction "INTB_1") (pintype "output"))
    )
    (net (code "19") (name "PMIC_ON_REQ") (class "Default")
      (node (ref "R15") (pin "1") (pinfunction "1_1") (pintype "passive"))
      (node (ref "U4") (pin "48") (pinfunction "PWRON_48") (pintype "input"))
    )
    (net (code "20") (name "PMIC_RESET") (class "Default")
      (node (ref "U4") (pin "3") (pinfunction "RESETBMCU_3") (pintype "output"))
    )
    (net (code "21") (name "PMIC_STBY_REQ") (class "Default")
      (node (ref "U4") (pin "4") (pinfunction "STANDBY_4") (pintype "input"))
    )
    (net (code "22") (name "SD_VSEL") (class "Default")
      (node (ref "R23") (pin "2") (pinfunction "2_2") (pintype "passive"))
      (node (ref "U4") (pin "2") (pinfunction "SD_VSEL_2") (pintype "input"))
    )
    (net (code "23") (name "SW2_OUT") (class "Default")
      (node (ref "C75") (pin "2") (pinfunction "2_2") (pintype "passive"))
      (node (ref "C76") (pin "2") (pinfunction "2_2") (pintype "passive"))
      (node (ref "L6") (pin "1") (pinfunction "1_1") (pintype "passive"))
      (node (ref "R19") (pin "1") (pinfunction "1_1") (pintype "passive"))
      (node (ref "U4") (pin "19") (pinfunction "SW2FB_19") (pintype "input"))
    )
    (net (code "24") (name "SW3_OUT") (class "Default")
      (node (ref "C53") (pin "2") (pinfunction "2_2") (pintype "passive"))
      (node (ref "C54") (pin "2") (pinfunction "2_2") (pintype "passive"))
      (node (ref "L4") (pin "1") (pinfunction "1_1") (pintype "passive"))
      (node (ref "R21") (pin "1") (pinfunction "1_1") (pintype "passive"))
      (node (ref "U4") (pin "27") (pinfunction "SW3FB_27") (pintype "input"))
    )
    (net (code "25") (name "SWA1_OUT") (class "Default")
      (node (ref "C51") (pin "2") (pinfunction "2_2") (pintype "passive"))
      (node (ref "C52") (pin "2") (pinfunction "2_2") (pintype "passive"))
      (node (ref "L3") (pin "1") (pinfunction "1_1") (pintype "passive"))
      (node (ref "R14") (pin "1") (pinfunction "1_1") (pintype "passive"))
      (node (ref "U4") (pin "6") (pinfunction "SW1AFB_6") (pintype "input"))
    )
    (net (code "26") (name "SWB1_OUT") (class "Default")
      (node (ref "C65") (pin "2") (pinfunction "2_2") (pintype "passive"))
      (node (ref "C66") (pin "2") (pinfunction "2_2") (pintype "passive"))
      (node (ref "L5") (pin "1") (pinfunction "1_1") (pintype "passive"))
      (node (ref "R18") (pin "1") (pinfunction "1_1") (pintype "passive"))
      (node (ref "U4") (pin "11") (pinfunction "SW1BFB_11") (pintype "input"))
    )
    (net (code "27") (name "V33_OUT") (class "Default")
      (node (ref "C67") (pin "2") (pinfunction "2_2") (pintype "passive"))
      (node (ref "R25") (pin "1") (pinfunction "1_1") (pintype "passive"))
      (node (ref "U4") (pin "32") (pinfunction "V33_32") (pintype "power_in"))
    )
    (net (code "28") (name "VCC_1V8") (class "Default")
      (node (ref "R19") (pin "2") (pinfunction "2_2") (pintype "passive"))
    )
    (net (code "29") (name "VCC_3V3_LP") (class "Default")
      (node (ref "R16") (pin "2") (pinfunction "2_2") (pintype "passive"))
      (node (ref "R17") (pin "2") (pinfunction "2_2") (pintype "passive"))
    )
    (net (code "30") (name "VCC_ARM") (class "Default")
      (node (ref "R14") (pin "2") (pinfunction "2_2") (pintype "passive"))
    )
    (net (code "31") (name "VCC_SD") (class "Default")
      (node (ref "R24") (pin "2") (pinfunction "2_2") (pintype "passive"))
    )
    (net (code "32") (name "VCC_SD_OUT") (class "Default")
      (node (ref "C63") (pin "2") (pinfunction "2_2") (pintype "passive"))
      (node (ref "R24") (pin "1") (pinfunction "1_1") (pintype "passive"))
      (node (ref "U4") (pin "33") (pinfunction "VCC_SD_33") (pintype "power_in"))
    )
    (net (code "33") (name "VCC_SOC") (class "Default")
      (node (ref "R18") (pin "2") (pinfunction "2_2") (pintype "passive"))
    )
    (net (code "34") (name "VDD_LPSR") (class "Default")
      (node (ref "R13") (pin "2") (pinfunction "2_2") (pintype "passive"))
    )
    (net (code "35") (name "VLDO1_OUT") (class "Default")
      (node (ref "C57") (pin "2") (pinfunction "2_2") (pintype "passive"))
      (node (ref "R13") (pin "1") (pinfunction "1_1") (pintype "passive"))
      (node (ref "U4") (pin "14") (pinfunction "VLDO1_14") (pintype "power_in"))
    )
    (net (code "36") (name "VLDO3_OUT") (class "Default")
      (node (ref "C59") (pin "2") (pinfunction "2_2") (pintype "passive"))
      (node (ref "R17") (pin "1") (pinfunction "1_1") (pintype "passive"))
      (node (ref "U4") (pin "20") (pinfunction "VLDO3_20") (pintype "power_in"))
    )
    (net (code "37") (name "VREFDDR_OUT") (class "Default")
      (node (ref "C71") (pin "2") (pinfunction "2_2") (pintype "passive"))
      (node (ref "R26") (pin "1") (pinfunction "1_1") (pintype "passive"))
      (node (ref "U4") (pin "25") (pinfunction "VREFDDR_25") (pintype "power_in"))
    )
    (net (code "38") (name "VSNVS") (class "Default")
      (node (ref "R15") (pin "2") (pinfunction "2_2") (pintype "passive"))
      (node (ref "R22") (pin "2") (pinfunction "2_2") (pintype "passive"))
    )
    (net (code "39") (name "VSNVS_OUT") (class "Default")
      (node (ref "C72") (pin "2") (pinfunction "2_2") (pintype "passive"))
      (node (ref "R22") (pin "1") (pinfunction "1_1") (pintype "passive"))
      (node (ref "U4") (pin "34") (pinfunction "VSNVS_34") (pintype "power_in"))
    )
    (net (code "40") (name "unconnected-(U4A-LDOG-Pad30)") (class "Default")
      (node (ref "U4") (pin "30") (pinfunction "LDOG_30") (pintype "output+no_connect"))
    )
    (net (code "41") (name "unconnected-(U4A-VLDO2-Pad15)") (class "Default")
      (node (ref "U4") (pin "15") (pinfunction "VLDO2_15") (pintype "power_in+no_connect"))
    )
    (net (code "42") (name "unconnected-(U4A-VLDO4-Pad22)") (class "Default")
      (node (ref "U4") (pin "22") (pinfunction "VLDO4_22") (pintype "power_in+no_connect"))
    )
    (net (code "43") (name "unconnected-(U4B-SWBSTFB-Pad37)") (class "Default")
      (node (ref "U4") (pin "37") (pinfunction "SWBSTFB_37") (pintype "input+no_connect"))
    )
    (net (code "44") (name "unconnected-(U4B-SWBSTLX-Pad35)") (class "Default")
      (node (ref "U4") (pin "35") (pinfunction "SWBSTLX_35") (pintype "power_in+no_connect"))
    )
  )
)
